# TPC.net
KiCad netlist of a schematic drawn in Altium Designer
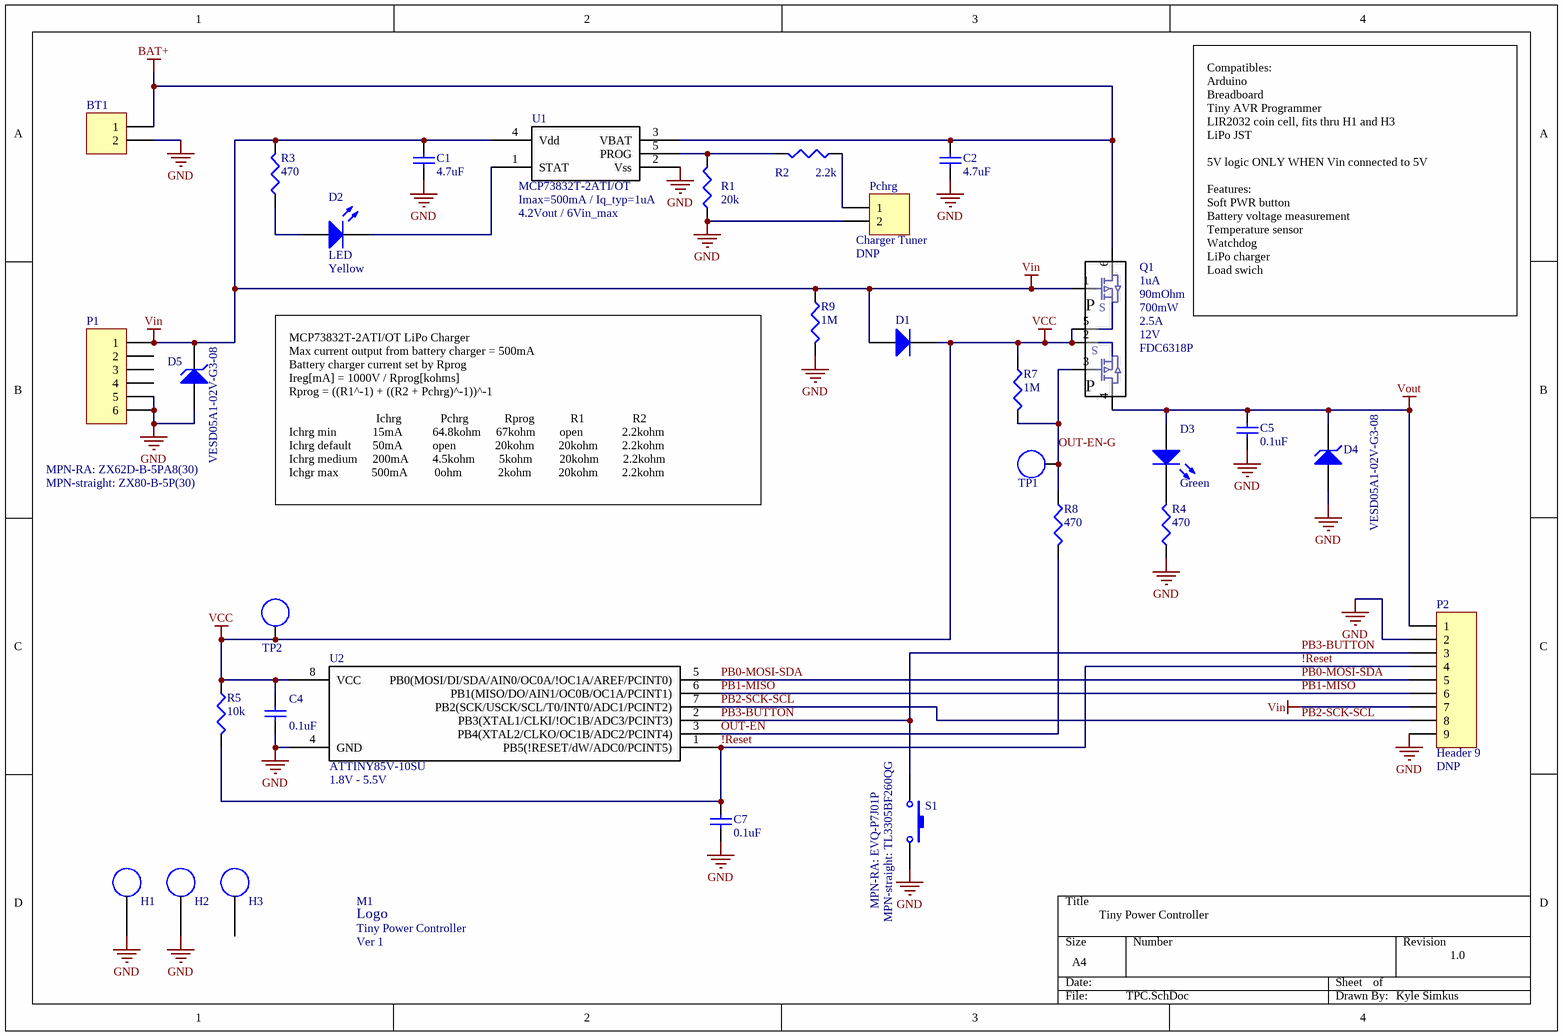
[diagram p0: TPC.SchDoc]

(export (version "E")
  (design (tool "Eeschema 10.0.6"))
  (components
    (comp (ref "BT1")
      (value "JST connector")
      (footprint "JST-DUAL-Batt - 2mm 3_5mm")
      (description "CONN HEADER VERT 2POS 2MM")
      (fields (field (name "MPN") "B2B-PH-K-S(LF)(SN)"))
      (libsource (lib "Miscellaneous Connectors") (part "Header 2"))
    )
    (comp (ref "C1")
      (value "4.7uF")
      (footprint "C0603")
      (description "CAP CER 4.7UF 10V X5R 0603")
      (fields (field (name "VOLTAGE") "V") (field (name "MPN") "CL10A475KP8NNNC"))
      (libsource (lib "Miscellaneous Devices") (part "Cap Semi"))
    )
    (comp (ref "C2")
      (value "4.7uF")
      (footprint "C0603")
      (description "CAP CER 4.7UF 10V X5R 0603")
      (fields (field (name "VOLTAGE") "V") (field (name "MPN") "CL10A475KP8NNNC"))
      (libsource (lib "Miscellaneous Devices") (part "Cap Semi"))
    )
    (comp (ref "C4")
      (value "0.1uF")
      (footprint "C0603")
      (description "CAP CER 0.1UF 16V X7R 0603")
      (fields (field (name "VOLTAGE") "V") (field (name "MPN") "CL10B104KO8NNNC"))
      (libsource (lib "Miscellaneous Devices") (part "Cap Semi"))
    )
    (comp (ref "C5")
      (value "0.1uF")
      (footprint "C0603")
      (description "CAP CER 0.1UF 16V X7R 0603")
      (fields (field (name "VOLTAGE") "V") (field (name "MPN") "CL10B104KO8NNNC"))
      (libsource (lib "Miscellaneous Devices") (part "Cap Semi"))
    )
    (comp (ref "C7")
      (value "0.1uF")
      (footprint "C0603")
      (description "CAP CER 0.1UF 16V X7R 0603")
      (fields (field (name "VOLTAGE") "V") (field (name "MPN") "CL10B104KO8NNNC"))
      (libsource (lib "Miscellaneous Devices") (part "Cap Semi"))
    )
    (comp (ref "D1")
      (value "Diode")
      (footprint "SOD128")
      (description "DIODE SCHOTTK 60V 3A SOD128/CFP5")
      (fields (field (name "MPN") "PMEG6030ELPX"))
      (libsource (lib "Miscellaneous Devices") (part "Diode"))
    )
    (comp (ref "D2")
      (value "LED")
      (footprint "0805 [2012] LED")
      (description "LED YELLOW CLEAR 0805 SMD")
      (fields (field (name "ALTIUM_VALUE") "Yellow") (field (name "MPN") "QTLP630C3TR"))
      (libsource (lib "Miscellaneous Devices") (part "LED2"))
    )
    (comp (ref "D3")
      (value "Green")
      (footprint "0805 [2012] LED")
      (description "LED GREEN CLEAR 0805 SMD")
      (fields (field (name "MPN") "QTLP630C4TR/FC17-21SYGC/S530-E2/TR8") (field (name "Comment") "LED"))
      (libsource (lib "Miscellaneous Devices") (part "LED2"))
    )
    (comp (ref "D4")
      (value "DIODE")
      (footprint "SOD523")
      (description "TVS DIODE 5VWM 12VC SOD523")
      (fields (field (name "MPN") "VESD05A1-02V-G3-08"))
      (libsource (lib "Miscellaneous Devices") (part "D Zener"))
    )
    (comp (ref "D5")
      (value "DIODE")
      (footprint "SOD523")
      (description "TVS DIODE 5VWM 12VC SOD523")
      (fields (field (name "MPN") "VESD05A1-02V-G3-08"))
      (libsource (lib "Miscellaneous Devices") (part "D Zener"))
    )
    (comp (ref "H1")
      (value "MountingHole")
      (footprint "Mounting-Hole-2-56")
      (libsource (lib "TPC") (part "MountingHole"))
    )
    (comp (ref "H2")
      (value "MountingHole")
      (footprint "Mounting-Hole-2-56")
      (libsource (lib "TPC") (part "MountingHole"))
    )
    (comp (ref "H3")
      (value "MountingHole")
      (footprint "Mounting-Hole-2-56 - isolated")
      (libsource (lib "TPC") (part "MountingHole"))
    )
    (comp (ref "M1")
      (value "Ver 1")
      (footprint "Logo-KAS")
      (description "Logo")
      (fields (field (name "FULLNAME") "Tiny Power Controller"))
      (libsource (lib "EG") (part "Logo-KAS"))
    )
    (comp (ref "P1")
      (value "USB micro")
      (footprint "USBmicro-DUAL Hirose Dual sided")
      (description "CONN RCPT USB2.0 MICRO B SMD R/A")
      (fields
        (field (name "MPN-RA") "ZX62D-B-5PA8(30)")
        (field (name "MPN-STRAIGHT") "ZX80-B-5P(30)")
        (field (name "MPN") "ZX62D-B-5PA8(30)")
      )
      (libsource (lib "Miscellaneous Connectors") (part "Header 6"))
    )
    (comp (ref "P2")
      (value "Header 9")
      (footprint "HDR1X9")
      (description "Header, 9-Pin")
      (fields (field (name "DNP") "DNP"))
      (libsource (lib "Miscellaneous Connectors") (part "Header 9"))
    )
    (comp (ref "Pchrg")
      (value "Charger Tuner")
      (footprint "HDR1X2")
      (description "Header, 2-Pin")
      (fields (field (name "DNP") "DNP"))
      (libsource (lib "") (part "Header 2_1"))
    )
    (comp (ref "Q1")
      (value "2x PMOS")
      (footprint "SOT-23-6")
      (description "MOSFET 2P-CH 12V 2.5A SSOT-6")
      (fields
        (field (name "IDSS") "1uA")
        (field (name "RDS") "90mOhm")
        (field (name "PMAX") "700mW")
        (field (name "ID") "2.5A")
        (field (name "VDSS") "12V")
        (field (name "MPN") "FDC6318P")
      )
      (libsource (lib "TPC") (part "MOSFET-P-x2"))
    )
    (comp (ref "R1")
      (value "20k")
      (footprint "R0603")
      (description "RES SMD 20K OHM 1% 1/10W 0603")
      (fields (field (name "MPN") "ERJ-3EKF2002V") (field (name "Comment") "RES"))
      (libsource (lib "Miscellaneous Devices") (part "Res3"))
    )
    (comp (ref "R2")
      (value "2.2k")
      (footprint "R0603")
      (description "RES SMD 2.2K OHM 1% 1/10W 0603")
      (fields (field (name "MPN") "ERJ3EKF2201V") (field (name "Comment") "RES"))
      (libsource (lib "Miscellaneous Devices") (part "Res3"))
    )
    (comp (ref "R3")
      (value "470")
      (footprint "R0603")
      (description "RES SMD 470 OHM 5% 1/10W 0603")
      (fields (field (name "MPN") "ERJ-3GEYJ471V") (field (name "Comment") "RES"))
      (libsource (lib "Miscellaneous Devices") (part "Res3"))
    )
    (comp (ref "R4")
      (value "470")
      (footprint "R0603")
      (description "RES SMD 470 OHM 5% 1/10W 0603")
      (fields (field (name "MPN") "ERJ-3GEYJ471V") (field (name "Comment") "RES"))
      (libsource (lib "Miscellaneous Devices") (part "Res3"))
    )
    (comp (ref "R5")
      (value "10k")
      (footprint "R0603")
      (description "Resistor")
      (fields (field (name "MPN") "ERJ-3GEYJ103V") (field (name "Comment") "RES"))
      (libsource (lib "Miscellaneous Devices") (part "Res3"))
    )
    (comp (ref "R7")
      (value "1M")
      (footprint "R0603")
      (description "RES SMD 1M OHM 5% 1/10W 0603")
      (fields (field (name "MPN") "ERJ-3GEYJ105V") (field (name "Comment") "RES"))
      (libsource (lib "Miscellaneous Devices") (part "Res3"))
    )
    (comp (ref "R8")
      (value "470")
      (footprint "R0603")
      (description "RES SMD 470 OHM 5% 1/10W 0603")
      (fields (field (name "MPN") "ERJ-3GEYJ471V") (field (name "Comment") "RES"))
      (libsource (lib "Miscellaneous Devices") (part "Res3"))
    )
    (comp (ref "R9")
      (value "1M")
      (footprint "R0603")
      (description "RES SMD 1M OHM 5% 1/10W 0603")
      (fields (field (name "MPN") "ERJ-3GEYJ105V") (field (name "Comment") "RES"))
      (libsource (lib "Miscellaneous Devices") (part "Res3"))
    )
    (comp (ref "S1")
      (value "BUTTON")
      (footprint "SW Multi TH")
      (description "SWITCH TACTILE SPST-NO 0.05A 12V")
      (fields
        (field (name "MPN-RA") "EVQ-P7J01P")
        (field (name "MPN-STRAIGHT") "TL3305BF260QG")
        (field (name "MPN") "EVQ-P7J01P")
      )
      (libsource (lib "Miscellaneous Devices") (part "SW-PB"))
    )
    (comp (ref "TP1")
      (value "TestPoint")
      (footprint "TestPoint-1_0-smt")
      (libsource (lib "TPC") (part "TestPoint"))
    )
    (comp (ref "TP2")
      (value "TestPoint")
      (footprint "TestPoint-1_0-smt")
      (libsource (lib "TPC") (part "TestPoint"))
    )
    (comp (ref "U1")
      (value "Charger")
      (footprint "SOT-23-5")
      (description "LiPo Charger 500mA 4.2V")
      (fields
        (field (name "CURRENT") "Imax=500mA / Iq_typ=1uA")
        (field (name "VOLTAGE") "4.2Vout / 6Vin_max")
        (field (name "MPN") "MCP73832T-2ATI/OT")
      )
      (libsource (lib "EG") (part "MCP73832T-2ATI/OT"))
    )
    (comp (ref "U2")
      (value "MCU")
      (footprint "8-SOIC-5.3mm")
      (description "IC MCU 8BIT 8KB FLASH 8SOIC")
      (fields (field (name "VOLTAGE") "1.8V - 5.5V") (field (name "MPN") "ATTINY85V-10SU"))
      (libsource (lib "ATP") (part "ATtiny85-20SU"))
    )
  )
  (nets
    (net (code "1") (name "/!Reset") (class "Default")
      (node (ref "C7") (pin "2") (pinfunction "2_2") (pintype "passive"))
      (node (ref "P2") (pin "4") (pinfunction "4_4") (pintype "passive"))
      (node (ref "R5") (pin "2") (pinfunction "2_2") (pintype "passive"))
      (node (ref "U2") (pin "1") (pinfunction "PB5(!RESET/dW/ADC0/PCINT5)_1") (pintype "passive"))
    )
    (net (code "2") (name "/OUT-EN") (class "Default")
      (node (ref "R8") (pin "2") (pinfunction "2_2") (pintype "passive"))
      (node (ref "U2") (pin "3") (pinfunction "PB4(XTAL2/CLKO/OC1B/ADC2/PCINT4)_3") (pintype "passive"))
    )
    (net (code "3") (name "/OUT-EN-G") (class "Default")
      (node (ref "Q1") (pin "3") (pinfunction "G_3") (pintype "passive"))
      (node (ref "R7") (pin "2") (pinfunction "2_2") (pintype "passive"))
      (node (ref "R8") (pin "1") (pinfunction "1_1") (pintype "passive"))
      (node (ref "TP1") (pin "0") (pinfunction "TestPoint_0") (pintype "passive"))
    )
    (net (code "4") (name "/PB0-MOSI-SDA") (class "Default")
      (node (ref "P2") (pin "5") (pinfunction "5_5") (pintype "passive"))
      (node (ref "U2") (pin "5") (pinfunction "PB0(MOSI/DI/SDA/AIN0/OC0A/!OC1A/AREF/PCINT0)_5") (pintype "passive"))
    )
    (net (code "5") (name "/PB1-MISO") (class "Default")
      (node (ref "P2") (pin "6") (pinfunction "6_6") (pintype "passive"))
      (node (ref "U2") (pin "6") (pinfunction "PB1(MISO/DO/AIN1/OC0B/OC1A/PCINT1)_6") (pintype "passive"))
    )
    (net (code "6") (name "/PB2-SCK-SCL") (class "Default")
      (node (ref "P2") (pin "8") (pinfunction "8_8") (pintype "passive"))
      (node (ref "U2") (pin "7") (pinfunction "PB2(SCK/USCK/SCL/T0/INT0/ADC1/PCINT2)_7") (pintype "passive"))
    )
    (net (code "7") (name "/PB3-BUTTON") (class "Default")
      (node (ref "P2") (pin "3") (pinfunction "3_3") (pintype "passive"))
      (node (ref "S1") (pin "2") (pinfunction "2_2") (pintype "passive"))
      (node (ref "U2") (pin "2") (pinfunction "PB3(XTAL1/CLKI/!OC1B/ADC3/PCINT3)_2") (pintype "passive"))
    )
    (net (code "8") (name "BAT+") (class "Default")
      (node (ref "BT1") (pin "1") (pinfunction "1_1") (pintype "passive"))
      (node (ref "C2") (pin "2") (pinfunction "2_2") (pintype "passive"))
      (node (ref "Q1") (pin "6") (pinfunction "D_6") (pintype "passive"))
      (node (ref "U1") (pin "3") (pinfunction "VBAT_3") (pintype "passive"))
    )
    (net (code "9") (name "GND") (class "Default")
      (node (ref "BT1") (pin "2") (pinfunction "2_2") (pintype "passive"))
      (node (ref "C1") (pin "1") (pinfunction "1_1") (pintype "passive"))
      (node (ref "C2") (pin "1") (pinfunction "1_1") (pintype "passive"))
      (node (ref "C4") (pin "1") (pinfunction "1_1") (pintype "passive"))
      (node (ref "C5") (pin "1") (pinfunction "1_1") (pintype "passive"))
      (node (ref "C7") (pin "1") (pinfunction "1_1") (pintype "passive"))
      (node (ref "D4") (pin "1") (pinfunction "A_1") (pintype "passive"))
      (node (ref "D5") (pin "1") (pinfunction "A_1") (pintype "passive"))
      (node (ref "H1") (pin "0") (pintype "passive"))
      (node (ref "H2") (pin "0") (pintype "passive"))
      (node (ref "P1") (pin "5") (pinfunction "5_5") (pintype "passive"))
      (node (ref "P1") (pin "6") (pinfunction "6_6") (pintype "passive"))
      (node (ref "P2") (pin "2") (pinfunction "2_2") (pintype "passive"))
      (node (ref "P2") (pin "9") (pinfunction "9_9") (pintype "passive"))
      (node (ref "Pchrg") (pin "2") (pinfunction "2_2") (pintype "passive"))
      (node (ref "R1") (pin "1") (pinfunction "1_1") (pintype "passive"))
      (node (ref "R4") (pin "1") (pinfunction "1_1") (pintype "passive"))
      (node (ref "R9") (pin "2") (pinfunction "2_2") (pintype "passive"))
      (node (ref "S1") (pin "1") (pinfunction "1_1") (pintype "passive"))
      (node (ref "U1") (pin "2") (pinfunction "Vss_2") (pintype "passive"))
      (node (ref "U2") (pin "4") (pinfunction "GND_4") (pintype "passive"))
    )
    (net (code "10") (name "Net-(D2-A)") (class "Default")
      (node (ref "D2") (pin "1") (pinfunction "A_1") (pintype "passive"))
      (node (ref "R3") (pin "1") (pinfunction "1_1") (pintype "passive"))
    )
    (net (code "11") (name "Net-(D2-K)") (class "Default")
      (node (ref "D2") (pin "2") (pinfunction "K_2") (pintype "passive"))
      (node (ref "U1") (pin "1") (pinfunction "STAT_1") (pintype "passive"))
    )
    (net (code "12") (name "Net-(D3-K)") (class "Default")
      (node (ref "D3") (pin "2") (pinfunction "K_2") (pintype "passive"))
      (node (ref "R4") (pin "2") (pinfunction "2_2") (pintype "passive"))
    )
    (net (code "13") (name "Net-(Pchrg-Pad1)") (class "Default")
      (node (ref "Pchrg") (pin "1") (pinfunction "1_1") (pintype "passive"))
      (node (ref "R2") (pin "1") (pinfunction "1_1") (pintype "passive"))
    )
    (net (code "14") (name "Net-(U1-PROG)") (class "Default")
      (node (ref "R1") (pin "2") (pinfunction "2_2") (pintype "passive"))
      (node (ref "R2") (pin "2") (pinfunction "2_2") (pintype "passive"))
      (node (ref "U1") (pin "5") (pinfunction "PROG_5") (pintype "passive"))
    )
    (net (code "15") (name "VCC") (class "Default")
      (node (ref "C4") (pin "2") (pinfunction "2_2") (pintype "passive"))
      (node (ref "D1") (pin "2") (pinfunction "K_2") (pintype "passive"))
      (node (ref "Q1") (pin "2") (pinfunction "S_2") (pintype "passive"))
      (node (ref "Q1") (pin "5") (pinfunction "S_5") (pintype "passive"))
      (node (ref "R5") (pin "1") (pinfunction "1_1") (pintype "passive"))
      (node (ref "R7") (pin "1") (pinfunction "1_1") (pintype "passive"))
      (node (ref "TP2") (pin "0") (pinfunction "TestPoint_0") (pintype "passive"))
      (node (ref "U2") (pin "8") (pinfunction "VCC_8") (pintype "passive"))
    )
    (net (code "16") (name "Vin") (class "Default")
      (node (ref "C1") (pin "2") (pinfunction "2_2") (pintype "passive"))
      (node (ref "D1") (pin "1") (pinfunction "A_1") (pintype "passive"))
      (node (ref "D5") (pin "2") (pinfunction "K_2") (pintype "passive"))
      (node (ref "P1") (pin "1") (pinfunction "1_1") (pintype "passive"))
      (node (ref "P2") (pin "7") (pinfunction "7_7") (pintype "passive"))
      (node (ref "Q1") (pin "1") (pinfunction "G_1") (pintype "passive"))
      (node (ref "R3") (pin "2") (pinfunction "2_2") (pintype "passive"))
      (node (ref "R9") (pin "1") (pinfunction "1_1") (pintype "passive"))
      (node (ref "U1") (pin "4") (pinfunction "Vdd_4") (pintype "passive"))
    )
    (net (code "17") (name "Vout") (class "Default")
      (node (ref "C5") (pin "2") (pinfunction "2_2") (pintype "passive"))
      (node (ref "D3") (pin "1") (pinfunction "A_1") (pintype "passive"))
      (node (ref "D4") (pin "2") (pinfunction "K_2") (pintype "passive"))
      (node (ref "P2") (pin "1") (pinfunction "1_1") (pintype "passive"))
      (node (ref "Q1") (pin "4") (pinfunction "D_4") (pintype "passive"))
    )
    (net (code "18") (name "unconnected-(H3-Pad0)") (class "Default")
      (node (ref "H3") (pin "0") (pintype "passive"))
    )
    (net (code "19") (name "unconnected-(P1-Pad2)") (class "Default")
      (node (ref "P1") (pin "2") (pinfunction "2_2") (pintype "passive"))
    )
    (net (code "20") (name "unconnected-(P1-Pad3)") (class "Default")
      (node (ref "P1") (pin "3") (pinfunction "3_3") (pintype "passive"))
    )
    (net (code "21") (name "unconnected-(P1-Pad4)") (class "Default")
      (node (ref "P1") (pin "4") (pinfunction "4_4") (pintype "passive"))
    )
  )
)
